# 09_Clock.net
KiCad netlist of a schematic drawn in Altium Designer
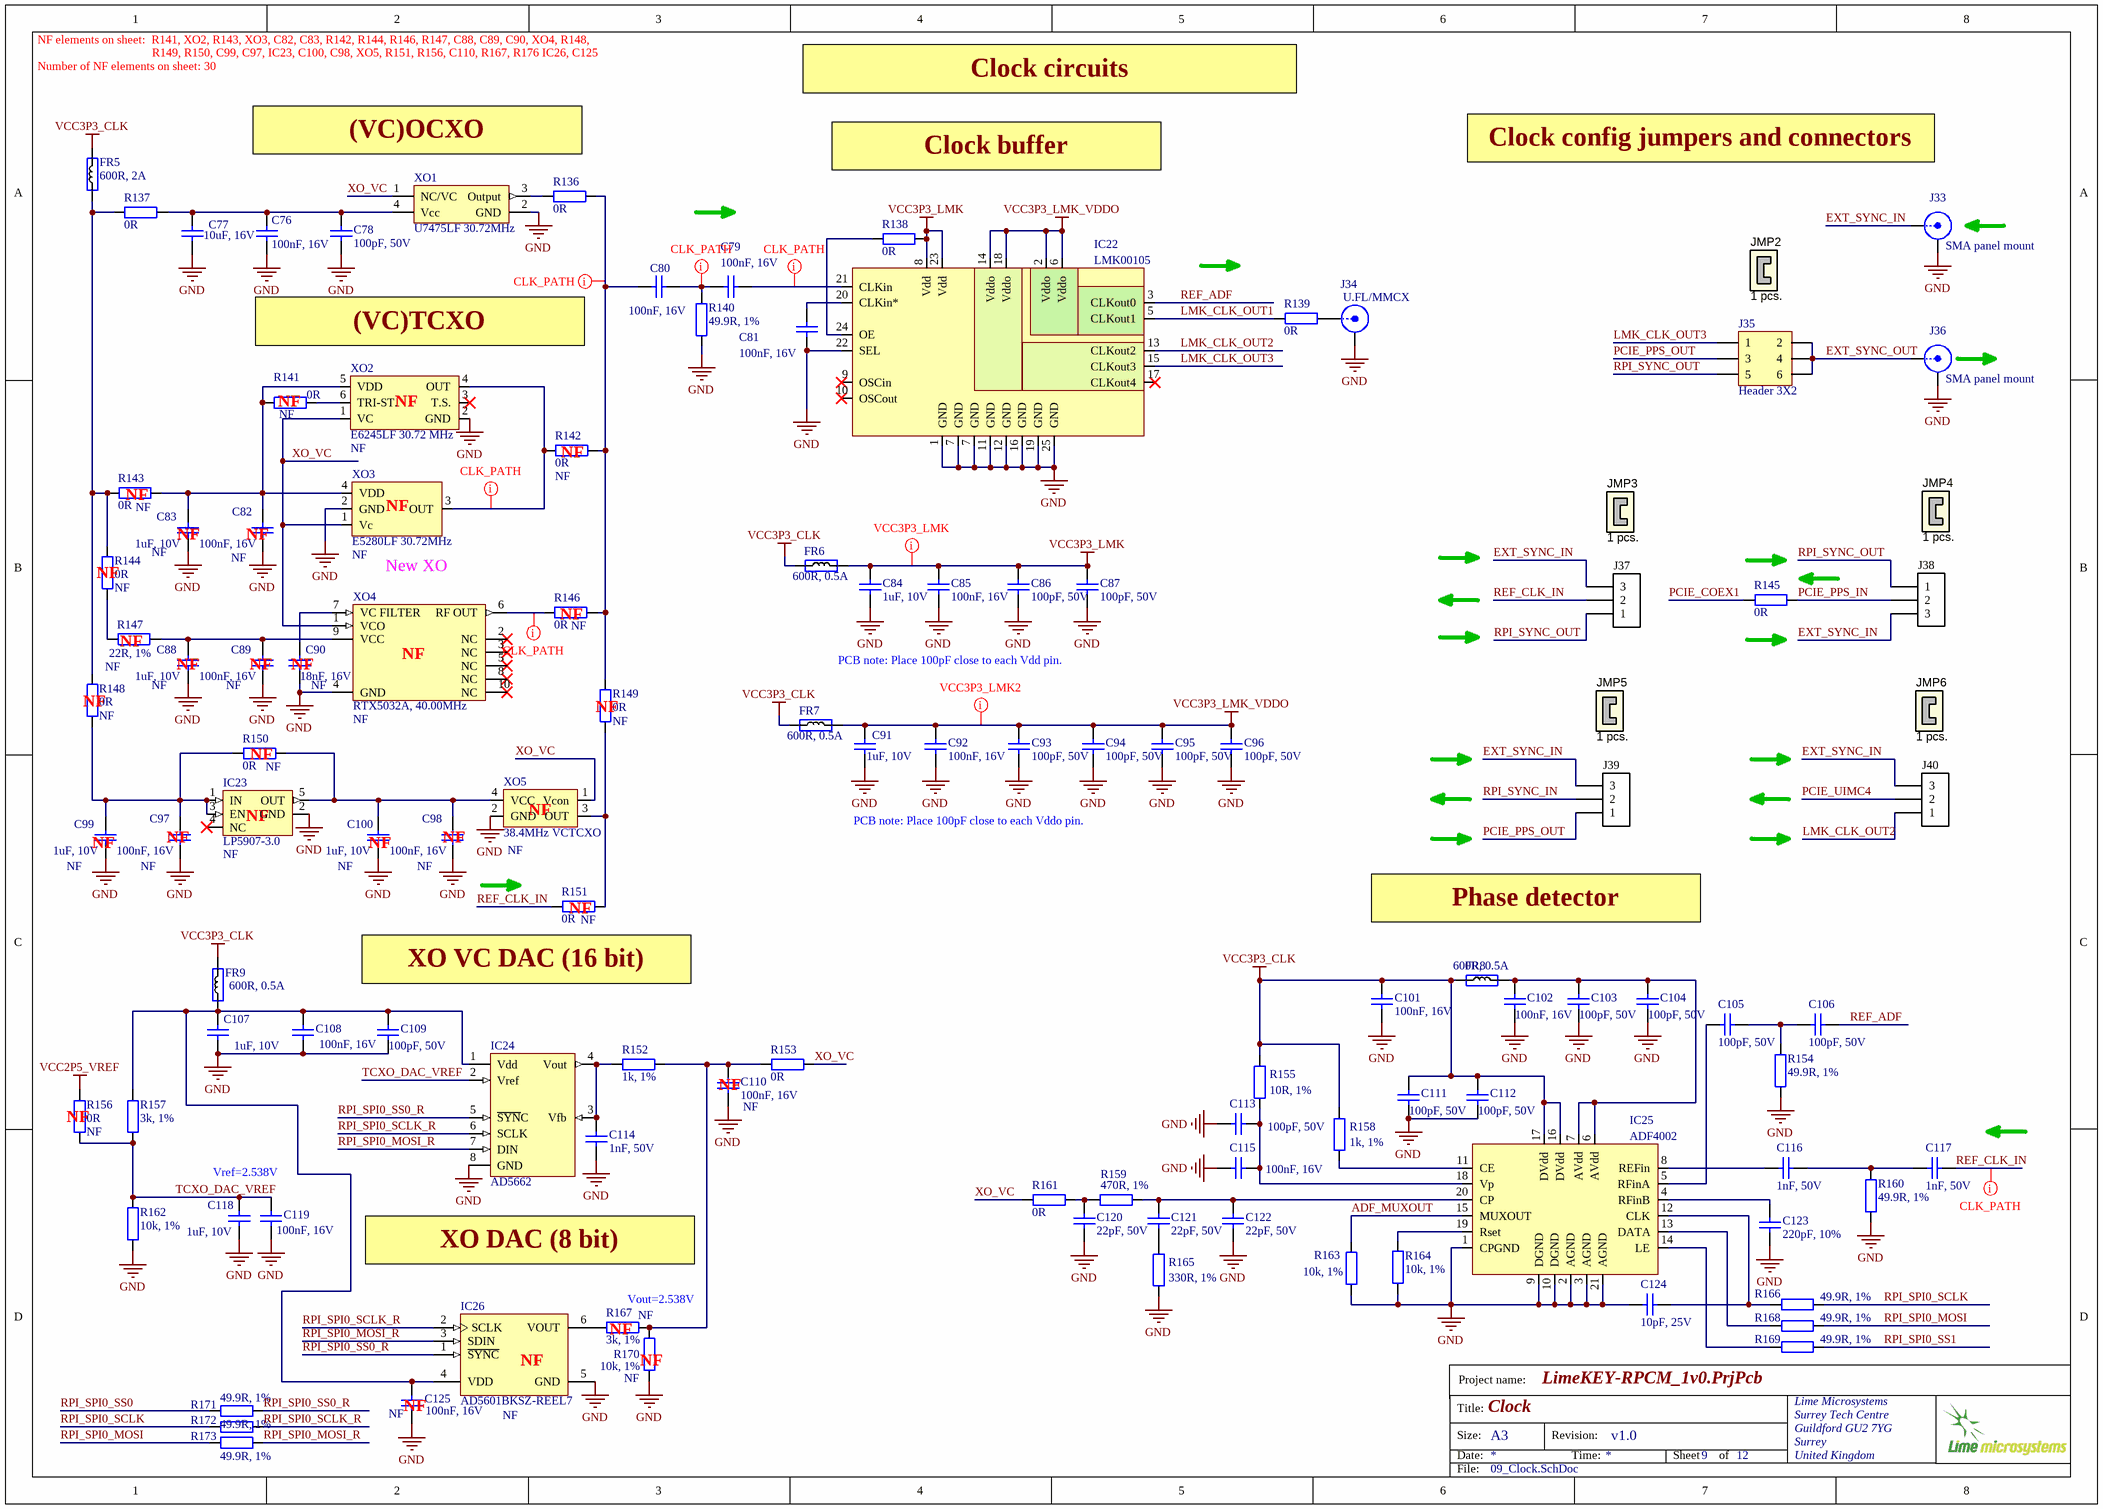
[diagram p0: 09_Clock.SchDoc]

(export (version "E")
  (design (tool "Eeschema 10.0.6"))
  (components
    (comp (ref "C76")
      (value "100nF, 16V")
      (footprint "CAP0402")
      (fields
        (field (name "MANUFACTURER") "Murata Electronics")
        (field (name "TOLERANCE") "10 %")
        (field (name "MANUFACTURER PART NUMBER") "GRM155R71C104KA88D")
      )
      (libsource (lib "LimeMicroAltiumLib_schLib") (part "Cap_0402"))
    )
    (comp (ref "C77")
      (value "10uF, 16V")
      (footprint "CAP0603")
      (fields (field (name "MANUFACTURER") "Yageo") (field (name "TOLERANCE") "±20%"))
      (libsource (lib "LimeMicroAltiumLib_schLib") (part "Cap_0603"))
    )
    (comp (ref "C78")
      (value "100pF, 50V")
      (footprint "CAP0402")
      (fields (field (name "TOLERANCE") "±5%") (field (name "MANUFACTURER") "Yageo"))
      (libsource (lib "LimeMicroAltiumLib_schLib") (part "Cap_0402"))
    )
    (comp (ref "C79")
      (value "100nF, 16V")
      (footprint "CAP0402")
      (fields
        (field (name "MANUFACTURER") "Murata Electronics")
        (field (name "TOLERANCE") "10 %")
        (field (name "MANUFACTURER PART NUMBER") "GRM155R71C104KA88D")
      )
      (libsource (lib "LimeMicroAltiumLib_schLib") (part "Cap_0402"))
    )
    (comp (ref "C80")
      (value "100nF, 16V")
      (footprint "CAP0402")
      (fields
        (field (name "MANUFACTURER") "Murata Electronics")
        (field (name "TOLERANCE") "10 %")
        (field (name "MANUFACTURER PART NUMBER") "GRM155R71C104KA88D")
      )
      (libsource (lib "LimeMicroAltiumLib_schLib") (part "Cap_0402"))
    )
    (comp (ref "C81")
      (value "100nF, 16V")
      (footprint "CAP0402")
      (fields
        (field (name "MANUFACTURER") "Murata Electronics")
        (field (name "TOLERANCE") "10 %")
        (field (name "MANUFACTURER PART NUMBER") "GRM155R71C104KA88D")
      )
      (libsource (lib "LimeMicroAltiumLib_schLib") (part "Cap_0402"))
    )
    (comp (ref "C82")
      (value "100nF, 16V")
      (footprint "CAP0402")
      (fields
        (field (name "ASSEMBLY INFO") "NF")
        (field (name "MANUFACTURER") "Murata Electronics")
        (field (name "TOLERANCE") "10 %")
        (field (name "MANUFACTURER PART NUMBER") "GRM155R71C104KA88D")
      )
      (libsource (lib "LimeMicroAltiumLib_schLib") (part "Cap_0402"))
    )
    (comp (ref "C83")
      (value "1uF, 10V")
      (footprint "CAP0402")
      (description "CAP CER 1UF 10V X5R 0402")
      (fields (field (name "ASSEMBLY INFO") "NF") (field (name "MANUFACTURER") "Yageo"))
      (libsource (lib "LimeMicroAltiumLib_schLib") (part "Cap_0402"))
    )
    (comp (ref "C84")
      (value "1uF, 10V")
      (footprint "CAP0402")
      (description "CAP CER 1UF 10V X5R 0402")
      (fields (field (name "MANUFACTURER") "Yageo") (field (name "TOLERANCE") "±20%"))
      (libsource (lib "LimeMicroAltiumLib_schLib") (part "Cap_0402"))
    )
    (comp (ref "C85")
      (value "100nF, 16V")
      (footprint "CAP0402")
      (fields
        (field (name "MANUFACTURER") "Murata Electronics")
        (field (name "TOLERANCE") "10 %")
        (field (name "MANUFACTURER PART NUMBER") "GRM155R71C104KA88D")
      )
      (libsource (lib "LimeMicroAltiumLib_schLib") (part "Cap_0402"))
    )
    (comp (ref "C86")
      (value "100pF, 50V")
      (footprint "CAP0402")
      (fields (field (name "MANUFACTURER") "Yageo") (field (name "TOLERANCE") "±5%"))
      (libsource (lib "LimeMicroAltiumLib_schLib") (part "Cap_0402"))
    )
    (comp (ref "C87")
      (value "100pF, 50V")
      (footprint "CAP0402")
      (fields (field (name "MANUFACTURER") "Yageo") (field (name "TOLERANCE") "±5%"))
      (libsource (lib "LimeMicroAltiumLib_schLib") (part "Cap_0402"))
    )
    (comp (ref "C88")
      (value "1uF, 10V")
      (footprint "CAP0402")
      (description "CAP CER 1UF 10V X5R 0402")
      (fields (field (name "ASSEMBLY INFO") "NF") (field (name "MANUFACTURER") "Yageo"))
      (libsource (lib "LimeMicroAltiumLib_schLib") (part "Cap_0402"))
    )
    (comp (ref "C89")
      (value "100nF, 16V")
      (footprint "CAP0402")
      (fields
        (field (name "ASSEMBLY INFO") "NF")
        (field (name "MANUFACTURER") "Murata Electronics")
        (field (name "TOLERANCE") "10 %")
        (field (name "MANUFACTURER PART NUMBER") "GRM155R71C104KA88D")
      )
      (libsource (lib "LimeMicroAltiumLib_schLib") (part "Cap_0402"))
    )
    (comp (ref "C90")
      (value "18nF, 16V")
      (footprint "CAP0402")
      (fields
        (field (name "ASSEMBLY INFO") "NF")
        (field (name "MANUFACTURER") "Yageo")
        (field (name "TOLERANCE") "±10%")
      )
      (libsource (lib "LimeMicroAltiumLib_schLib") (part "Cap_0402"))
    )
    (comp (ref "C91")
      (value "1uF, 10V")
      (footprint "CAP0402")
      (description "CAP CER 1UF 10V X5R 0402")
      (fields (field (name "MANUFACTURER") "Yageo") (field (name "TOLERANCE") "±20%"))
      (libsource (lib "LimeMicroAltiumLib_schLib") (part "Cap_0402"))
    )
    (comp (ref "C92")
      (value "100nF, 16V")
      (footprint "CAP0402")
      (fields
        (field (name "MANUFACTURER") "Murata Electronics")
        (field (name "TOLERANCE") "10 %")
        (field (name "MANUFACTURER PART NUMBER") "GRM155R71C104KA88D")
      )
      (libsource (lib "LimeMicroAltiumLib_schLib") (part "Cap_0402"))
    )
    (comp (ref "C93")
      (value "100pF, 50V")
      (footprint "CAP0402")
      (fields (field (name "MANUFACTURER") "Yageo") (field (name "TOLERANCE") "±5%"))
      (libsource (lib "LimeMicroAltiumLib_schLib") (part "Cap_0402"))
    )
    (comp (ref "C94")
      (value "100pF, 50V")
      (footprint "CAP0402")
      (fields (field (name "MANUFACTURER") "Yageo") (field (name "TOLERANCE") "±5%"))
      (libsource (lib "LimeMicroAltiumLib_schLib") (part "Cap_0402"))
    )
    (comp (ref "C95")
      (value "100pF, 50V")
      (footprint "CAP0402")
      (fields (field (name "MANUFACTURER") "Yageo") (field (name "TOLERANCE") "±5%"))
      (libsource (lib "LimeMicroAltiumLib_schLib") (part "Cap_0402"))
    )
    (comp (ref "C96")
      (value "100pF, 50V")
      (footprint "CAP0402")
      (fields (field (name "MANUFACTURER") "Yageo") (field (name "TOLERANCE") "±5%"))
      (libsource (lib "LimeMicroAltiumLib_schLib") (part "Cap_0402"))
    )
    (comp (ref "C97")
      (value "100nF, 16V")
      (footprint "CAP0402")
      (fields
        (field (name "ASSEMBLY INFO") "NF")
        (field (name "MANUFACTURER") "Murata Electronics")
        (field (name "TOLERANCE") "10 %")
        (field (name "MANUFACTURER PART NUMBER") "GRM155R71C104KA88D")
      )
      (libsource (lib "") (part "Cap_0402_1"))
    )
    (comp (ref "C98")
      (value "100nF, 16V")
      (footprint "CAP0402")
      (fields
        (field (name "ASSEMBLY INFO") "NF")
        (field (name "MANUFACTURER") "Murata Electronics")
        (field (name "TOLERANCE") "10 %")
        (field (name "MANUFACTURER PART NUMBER") "GRM155R71C104KA88D")
      )
      (libsource (lib "") (part "Cap_0402_1"))
    )
    (comp (ref "C99")
      (value "1uF, 10V")
      (footprint "CAP0402")
      (fields (field (name "ASSEMBLY INFO") "NF") (field (name "MANUFACTURER") "Yageo"))
      (libsource (lib "") (part "Cap_0402_1"))
    )
    (comp (ref "C100")
      (value "1uF, 10V")
      (footprint "CAP0402")
      (fields (field (name "ASSEMBLY INFO") "NF") (field (name "MANUFACTURER") "Yageo"))
      (libsource (lib "") (part "Cap_0402_1"))
    )
    (comp (ref "C101")
      (value "100nF, 16V")
      (footprint "CAP0402")
      (fields
        (field (name "MANUFACTURER") "Murata Electronics")
        (field (name "TOLERANCE") "10 %")
        (field (name "MANUFACTURER PART NUMBER") "GRM155R71C104KA88D")
      )
      (libsource (lib "LimeMicroAltiumLib_schLib") (part "Cap_0402"))
    )
    (comp (ref "C102")
      (value "100nF, 16V")
      (footprint "CAP0402")
      (fields
        (field (name "MANUFACTURER") "Murata Electronics")
        (field (name "TOLERANCE") "10 %")
        (field (name "MANUFACTURER PART NUMBER") "GRM155R71C104KA88D")
      )
      (libsource (lib "LimeMicroAltiumLib_schLib") (part "Cap_0402"))
    )
    (comp (ref "C103")
      (value "100pF, 50V")
      (footprint "CAP0402")
      (fields (field (name "MANUFACTURER") "Yageo") (field (name "TOLERANCE") "±5%"))
      (libsource (lib "LimeMicroAltiumLib_schLib") (part "Cap_0402"))
    )
    (comp (ref "C104")
      (value "100pF, 50V")
      (footprint "CAP0402")
      (fields (field (name "MANUFACTURER") "Yageo") (field (name "TOLERANCE") "±5%"))
      (libsource (lib "LimeMicroAltiumLib_schLib") (part "Cap_0402"))
    )
    (comp (ref "C105")
      (value "100pF, 50V")
      (footprint "CAP0402")
      (fields (field (name "MANUFACTURER") "Yageo") (field (name "TOLERANCE") "±5%"))
      (libsource (lib "LimeMicroAltiumLib_schLib") (part "Cap_0402"))
    )
    (comp (ref "C106")
      (value "100pF, 50V")
      (footprint "CAP0402")
      (fields (field (name "MANUFACTURER") "Yageo") (field (name "TOLERANCE") "±5%"))
      (libsource (lib "LimeMicroAltiumLib_schLib") (part "Cap_0402"))
    )
    (comp (ref "C107")
      (value "1uF, 10V")
      (footprint "CAP0402")
      (description "CAP CER 1UF 10V X5R 0402")
      (fields (field (name "MANUFACTURER") "Yageo") (field (name "TOLERANCE") "±20%"))
      (libsource (lib "LimeMicroAltiumLib_schLib") (part "Cap_0402"))
    )
    (comp (ref "C108")
      (value "100nF, 16V")
      (footprint "CAP0402")
      (fields
        (field (name "TOLERANCE") "10 %")
        (field (name "MANUFACTURER") "Murata Electronics")
        (field (name "MANUFACTURER PART NUMBER") "GRM155R71C104KA88D")
      )
      (libsource (lib "LimeFPGAboard_schLib") (part "Cap_0603"))
    )
    (comp (ref "C109")
      (value "100pF, 50V")
      (footprint "CAP0402")
      (fields (field (name "MANUFACTURER") "Yageo") (field (name "TOLERANCE") "±5%"))
      (libsource (lib "LimeMicroAltiumLib_schLib") (part "Cap_0402"))
    )
    (comp (ref "C110")
      (value "100nF, 16V")
      (footprint "CAP0402")
      (fields
        (field (name "ASSEMBLY INFO") "NF")
        (field (name "MANUFACTURER") "Murata Electronics")
        (field (name "TOLERANCE") "10 %")
        (field (name "MANUFACTURER PART NUMBER") "GRM155R71C104KA88D")
      )
      (libsource (lib "LimeMicroAltiumLib_schLib") (part "Cap_0402"))
    )
    (comp (ref "C111")
      (value "100pF, 50V")
      (footprint "CAP0402")
      (fields (field (name "MANUFACTURER") "Yageo") (field (name "TOLERANCE") "±5%"))
      (libsource (lib "LimeMicroAltiumLib_schLib") (part "Cap_0402"))
    )
    (comp (ref "C112")
      (value "100pF, 50V")
      (footprint "CAP0402")
      (fields (field (name "MANUFACTURER") "Yageo") (field (name "TOLERANCE") "±5%"))
      (libsource (lib "LimeMicroAltiumLib_schLib") (part "Cap_0402"))
    )
    (comp (ref "C113")
      (value "100pF, 50V")
      (footprint "CAP0402")
      (fields (field (name "MANUFACTURER") "Yageo") (field (name "TOLERANCE") "±5%"))
      (libsource (lib "LimeMicroAltiumLib_schLib") (part "Cap_0402"))
    )
    (comp (ref "C114")
      (value "1nF, 50V")
      (footprint "CAP0402")
      (fields
        (field (name "TOLERANCE") "±10%")
        (field (name "MANUFACTURER") "Murata Electronics North America")
      )
      (libsource (lib "LimeMicroAltiumLib_schLib") (part "Cap_0402"))
    )
    (comp (ref "C115")
      (value "100nF, 16V")
      (footprint "CAP0402")
      (fields
        (field (name "MANUFACTURER") "Murata Electronics")
        (field (name "TOLERANCE") "10 %")
        (field (name "MANUFACTURER PART NUMBER") "GRM155R71C104KA88D")
      )
      (libsource (lib "LimeMicroAltiumLib_schLib") (part "Cap_0402"))
    )
    (comp (ref "C116")
      (value "1nF, 50V")
      (footprint "CAP0402")
      (fields
        (field (name "TOLERANCE") "±10%")
        (field (name "MANUFACTURER") "Murata Electronics North America")
      )
      (libsource (lib "LimeMicroAltiumLib_schLib") (part "Cap_0402"))
    )
    (comp (ref "C117")
      (value "1nF, 50V")
      (footprint "CAP0402")
      (fields
        (field (name "TOLERANCE") "±10%")
        (field (name "MANUFACTURER") "Murata Electronics North America")
      )
      (libsource (lib "LimeMicroAltiumLib_schLib") (part "Cap_0402"))
    )
    (comp (ref "C118")
      (value "1uF, 10V")
      (footprint "CAP0402")
      (description "CAP CER 1UF 10V X5R 0402")
      (fields (field (name "MANUFACTURER") "Yageo") (field (name "TOLERANCE") "±20%"))
      (libsource (lib "LimeMicroAltiumLib_schLib") (part "Cap_0402"))
    )
    (comp (ref "C119")
      (value "100nF, 16V")
      (footprint "CAP0402")
      (fields
        (field (name "TOLERANCE") "10 %")
        (field (name "MANUFACTURER") "Murata Electronics")
        (field (name "MANUFACTURER PART NUMBER") "GRM155R71C104KA88D")
      )
      (libsource (lib "LimeFPGAboard_schLib") (part "Cap_0603"))
    )
    (comp (ref "C120")
      (value "22pF, 50V")
      (footprint "CAP0402")
      (fields (field (name "TOLERANCE") "±5%") (field (name "MANUFACTURER") "Yageo"))
      (libsource (lib "LimeMicroAltiumLib_schLib") (part "Cap_0402"))
    )
    (comp (ref "C121")
      (value "22pF, 50V")
      (footprint "CAP0402")
      (fields (field (name "TOLERANCE") "±5%") (field (name "MANUFACTURER") "Yageo"))
      (libsource (lib "LimeMicroAltiumLib_schLib") (part "Cap_0402"))
    )
    (comp (ref "C122")
      (value "22pF, 50V")
      (footprint "CAP0402")
      (fields (field (name "TOLERANCE") "±5%") (field (name "MANUFACTURER") "Yageo"))
      (libsource (lib "LimeMicroAltiumLib_schLib") (part "Cap_0402"))
    )
    (comp (ref "C123")
      (value "220pF, 10%")
      (footprint "CAP0402")
      (fields (field (name "MANUFACTURER") "Yageo") (field (name "TOLERANCE") "±10%"))
      (libsource (lib "LimeMicroAltiumLib_schLib") (part "Cap_0402"))
    )
    (comp (ref "C124")
      (value "10pF, 25V")
      (footprint "CAP0402")
      (fields (field (name "MANUFACTURER") "AVX"))
      (libsource (lib "LimeMicroAltiumLib_schLib") (part "Cap_0402"))
    )
    (comp (ref "C125")
      (value "100nF, 16V")
      (footprint "CAP0402")
      (fields
        (field (name "TOLERANCE") "10 %")
        (field (name "MANUFACTURER") "Murata Electronics")
        (field (name "MANUFACTURER PART NUMBER") "GRM155R71C104KA88D")
        (field (name "ASSEMBLY INFO") "NF")
      )
      (libsource (lib "LimeFPGAboard_schLib") (part "Cap_0603"))
    )
    (comp (ref "FR5")
      (value "600R, 2A")
      (footprint "RES0805")
      (fields (field (name "MANUFACTURER") "TDK Corporation"))
      (libsource (lib "LimeFPGAboard_schLib") (part "Ferrite"))
    )
    (comp (ref "FR6")
      (value "600R, 0.5A")
      (footprint "RES0402")
      (fields (field (name "MANUFACTURER") "Murata") (field (name "TOLERANCE") "25%"))
      (libsource (lib "LimeMicroAltiumLib_schLib") (part "Ferrite"))
    )
    (comp (ref "FR7")
      (value "600R, 0.5A")
      (footprint "RES0402")
      (fields (field (name "MANUFACTURER") "Murata") (field (name "TOLERANCE") "25%"))
      (libsource (lib "LimeMicroAltiumLib_schLib") (part "Ferrite"))
    )
    (comp (ref "FR8")
      (value "600R, 0.5A")
      (footprint "RES0402")
      (fields (field (name "MANUFACTURER") "Murata") (field (name "TOLERANCE") "25%"))
      (libsource (lib "LimeMicroAltiumLib_schLib") (part "Ferrite"))
    )
    (comp (ref "FR9")
      (value "600R, 0.5A")
      (footprint "RES0402")
      (fields (field (name "MANUFACTURER") "Murata") (field (name "TOLERANCE") "25%"))
      (libsource (lib "LimeMicroAltiumLib_schLib") (part "Ferrite"))
    )
    (comp (ref "IC22")
      (value "LMK00105")
      (footprint "LMK00105SQ")
      (fields (field (name "MANUFACTURER") "Texas Instruments"))
      (libsource (lib "LimeMicroAltiumLib_schLib") (part "LMK00105"))
    )
    (comp (ref "IC23")
      (value "LP5907-3.0")
      (footprint "SOT23-5")
      (fields (field (name "MANUFACTURER") "Texas Instruments") (field (name "ASSEMBLY INFO") "NF"))
      (libsource (lib "LimeMicroAltiumLib_schLib_r01") (part "LP5907"))
    )
    (comp (ref "IC24")
      (value "AD5662")
      (footprint "AD5662_SOT23-8")
      (fields (field (name "MANUFACTURER") "Analog Devices Inc."))
      (libsource (lib "LimeMicroAltiumLib_schLib") (part "AD5662"))
    )
    (comp (ref "IC25")
      (value "ADF4002")
      (footprint "ADF4002")
      (fields (field (name "MANUFACTURER") "Analog Devices Inc"))
      (libsource (lib "LimeMicroAltiumLib_schLib") (part "ADF4002"))
    )
    (comp (ref "IC26")
      (value "AD5601BKSZ-REEL7")
      (footprint "AD5601_SOT23-6")
      (fields
        (field (name "GENERIC PART NUMBER") "AD5601")
        (field (name "MANUFACTURER") "Analog Devices")
        (field (name "ASSEMBLY INFO") "NF")
      )
      (libsource (lib "LimeMicroAltiumLib_schLib") (part "AD5601BKSZ-REEL7"))
    )
    (comp (ref "J33")
      (value "SMA panel mount")
      (footprint "SMA_connector_side")
      (description "CONN SMA JACK STR 50OHM EDGE MNT")
      (fields (field (name "MANUFACTURER") "Linx"))
      (libsource (lib "LimeMicroAltiumLib_schLib") (part "RF_IF_connector"))
    )
    (comp (ref "J34")
      (value "U.FL/MMCX")
      (footprint "MMCX_UFL_conn_u")
      (description "CONN UMC RCPT STR 50 OHM SMD")
      (fields (field (name "MANUFACTURER") "Molex, LLC"))
      (libsource (lib "") (part "RF_IF_connector_1"))
    )
    (comp (ref "J35")
      (value "Header 3X2")
      (footprint "Header3x2")
      (description "Header, 2-Pin, Dual row")
      (fields
        (field (name "MANUFACTURER PART NUMBER") "PH2-06-UA")
        (field (name "MANUFACTURER") "Adam Equipment")
      )
      (libsource (lib "LimeMicroAltiumLib_schLib_r01") (part "Header 3X2"))
    )
    (comp (ref "J36")
      (value "SMA panel mount")
      (footprint "SMA_connector_side")
      (description "CONN SMA JACK STR 50OHM EDGE MNT")
      (fields (field (name "MANUFACTURER") "Linx"))
      (libsource (lib "LimeMicroAltiumLib_schLib") (part "RF_IF_connector"))
    )
    (comp (ref "J37")
      (value "Header 3x1 pin")
      (footprint "HDR_1x3")
      (description "Header, 3-pin")
      (fields
        (field (name "MANUFACTURER PART NUMBER") "61300311121")
        (field (name "MANUFACTURER") "Wurth Electronics")
      )
      (libsource (lib "") (part "Header3P_1"))
    )
    (comp (ref "J38")
      (value "Header 3x1 pin")
      (footprint "HDR_1x3")
      (description "Header, 3-pin")
      (fields
        (field (name "MANUFACTURER PART NUMBER") "61300311121")
        (field (name "MANUFACTURER") "Wurth Electronics")
      )
      (libsource (lib "LimeMicroAltiumLib_schLib_r04") (part "Header3P"))
    )
    (comp (ref "J39")
      (value "Header 3x1 pin")
      (footprint "HDR_1x3")
      (description "Header, 3-pin")
      (fields
        (field (name "MANUFACTURER PART NUMBER") "61300311121")
        (field (name "MANUFACTURER") "Wurth Electronics")
      )
      (libsource (lib "") (part "Header3P_1"))
    )
    (comp (ref "J40")
      (value "Header 3x1 pin")
      (footprint "HDR_1x3")
      (description "Header, 3-pin")
      (fields
        (field (name "MANUFACTURER PART NUMBER") "61300311121")
        (field (name "MANUFACTURER") "Wurth Electronics")
      )
      (libsource (lib "") (part "Header3P_1"))
    )
    (comp (ref "JMP2")
      (value "1 pcs.")
      (description "Shorting Jumper, 2-position, 1.27mm pitch")
      (fields (field (name "MANUFACTURER") "Sullins"))
      (libsource (lib "LimeMicroAltiumLib_schLib") (part "JUMP_2P_CONN_HEADER"))
    )
    (comp (ref "JMP3")
      (value "1 pcs.")
      (description "Shorting Jumper, 2-position, 1.27mm pitch")
      (fields (field (name "MANUFACTURER") "Sullins"))
      (libsource (lib "LimeMicroAltiumLib_schLib") (part "JUMP_2P_CONN_HEADER"))
    )
    (comp (ref "JMP4")
      (value "1 pcs.")
      (description "Shorting Jumper, 2-position, 1.27mm pitch")
      (fields (field (name "MANUFACTURER") "Sullins"))
      (libsource (lib "LimeMicroAltiumLib_schLib") (part "JUMP_2P_CONN_HEADER"))
    )
    (comp (ref "JMP5")
      (value "1 pcs.")
      (description "Shorting Jumper, 2-position, 1.27mm pitch")
      (fields (field (name "MANUFACTURER") "Sullins"))
      (libsource (lib "LimeMicroAltiumLib_schLib") (part "JUMP_2P_CONN_HEADER"))
    )
    (comp (ref "JMP6")
      (value "1 pcs.")
      (description "Shorting Jumper, 2-position, 1.27mm pitch")
      (fields (field (name "MANUFACTURER") "Sullins"))
      (libsource (lib "LimeMicroAltiumLib_schLib") (part "JUMP_2P_CONN_HEADER"))
    )
    (comp (ref "R136")
      (value "0R")
      (footprint "RES0402_v2")
      (fields (field (name "MANUFACTURER") "Yageo") (field (name "TOLERANCE") "Jumper"))
      (libsource (lib "LimeMicroAltiumLib_schLib") (part "Res_0402"))
    )
    (comp (ref "R137")
      (value "0R")
      (footprint "RES0402")
      (fields (field (name "MANUFACTURER") "Yageo") (field (name "TOLERANCE") "Jumper"))
      (libsource (lib "LimeMicroAltiumLib_schLib") (part "Res_0402"))
    )
    (comp (ref "R138")
      (value "0R")
      (footprint "RES0402")
      (fields (field (name "MANUFACTURER") "Yageo") (field (name "TOLERANCE") "Jumper"))
      (libsource (lib "LimeMicroAltiumLib_schLib") (part "Res_0402"))
    )
    (comp (ref "R139")
      (value "0R")
      (footprint "RES0402")
      (fields (field (name "MANUFACTURER") "Yageo") (field (name "TOLERANCE") "Jumper"))
      (libsource (lib "") (part "Res_0402_1"))
    )
    (comp (ref "R140")
      (value "49.9R, 1%")
      (footprint "RES0402")
      (fields
        (field (name "TOLERANCE") "±1%")
        (field (name "MANUFACTURER") "Samsung Electro-Mechanics America, Inc.")
      )
      (libsource (lib "LimeMicroAltiumLib_schLib") (part "Res_0402"))
    )
    (comp (ref "R141")
      (value "0R")
      (footprint "RES0402")
      (fields
        (field (name "ASSEMBLY INFO") "NF")
        (field (name "MANUFACTURER") "Yageo")
        (field (name "TOLERANCE") "Jumper")
      )
      (libsource (lib "LimeMicroAltiumLib_schLib") (part "Res_0402"))
    )
    (comp (ref "R142")
      (value "0R")
      (footprint "RES0402_v2")
      (fields
        (field (name "ASSEMBLY INFO") "NF")
        (field (name "MANUFACTURER") "Yageo")
        (field (name "TOLERANCE") "Jumper")
      )
      (libsource (lib "LimeMicroAltiumLib_schLib") (part "Res_0402"))
    )
    (comp (ref "R143")
      (value "0R")
      (footprint "RES0402")
      (fields
        (field (name "MANUFACTURER") "Yageo")
        (field (name "TOLERANCE") "Jumper")
        (field (name "ASSEMBLY INFO") "NF")
      )
      (libsource (lib "LimeMicroAltiumLib_schLib") (part "Res_0402"))
    )
    (comp (ref "R144")
      (value "0R")
      (footprint "RES0402")
      (fields
        (field (name "ASSEMBLY INFO") "NF")
        (field (name "MANUFACTURER") "Yageo")
        (field (name "TOLERANCE") "Jumper")
      )
      (libsource (lib "LimeMicroAltiumLib_schLib") (part "Res_0402"))
    )
    (comp (ref "R145")
      (value "0R")
      (footprint "RES0402")
      (fields (field (name "MANUFACTURER") "Yageo") (field (name "TOLERANCE") "Jumper"))
      (libsource (lib "") (part "Res_0402_1"))
    )
    (comp (ref "R146")
      (value "0R")
      (footprint "RES0402_v2")
      (fields
        (field (name "ASSEMBLY INFO") "NF")
        (field (name "MANUFACTURER") "Yageo")
        (field (name "TOLERANCE") "Jumper")
      )
      (libsource (lib "LimeMicroAltiumLib_schLib") (part "Res_0402"))
    )
    (comp (ref "R147")
      (value "22R, 1%")
      (footprint "RES0402")
      (fields
        (field (name "TOLERANCE") "±1%")
        (field (name "MANUFACTURER") "Yageo")
        (field (name "ASSEMBLY INFO") "NF")
      )
      (libsource (lib "LimeFPGAboard_schLib") (part "Res_0402"))
    )
    (comp (ref "R148")
      (value "0R")
      (footprint "RES0402")
      (fields
        (field (name "MANUFACTURER") "Yageo")
        (field (name "TOLERANCE") "Jumper")
        (field (name "ASSEMBLY INFO") "NF")
      )
      (libsource (lib "") (part "Res_0402_1"))
    )
    (comp (ref "R149")
      (value "0R")
      (footprint "RES0402_v2")
      (fields
        (field (name "ASSEMBLY INFO") "NF")
        (field (name "MANUFACTURER") "Yageo")
        (field (name "TOLERANCE") "Jumper")
      )
      (libsource (lib "") (part "Res_0402_1"))
    )
    (comp (ref "R150")
      (value "0R")
      (footprint "RES0402")
      (fields
        (field (name "MANUFACTURER") "Yageo")
        (field (name "TOLERANCE") "Jumper")
        (field (name "ASSEMBLY INFO") "NF")
      )
      (libsource (lib "") (part "Res_0402_1"))
    )
    (comp (ref "R151")
      (value "0R")
      (footprint "RES0402_v2")
      (fields
        (field (name "ASSEMBLY INFO") "NF")
        (field (name "MANUFACTURER") "Yageo")
        (field (name "TOLERANCE") "Jumper")
      )
      (libsource (lib "LimeMicroAltiumLib_schLib") (part "Res_0402"))
    )
    (comp (ref "R152")
      (value "1k, 1%")
      (footprint "RES0402")
      (fields (field (name "MANUFACTURER") "Stackpole Electronics Inc") (field (name "TOLERANCE") "±1%"))
      (libsource (lib "LimeMicroAltiumLib_schLib") (part "Res_0402"))
    )
    (comp (ref "R153")
      (value "0R")
      (footprint "RES0402")
      (fields (field (name "MANUFACTURER") "Yageo") (field (name "TOLERANCE") "Jumper"))
      (libsource (lib "LimeMicroAltiumLib_schLib") (part "Res_0402"))
    )
    (comp (ref "R154")
      (value "49.9R, 1%")
      (footprint "RES0402")
      (fields
        (field (name "TOLERANCE") "±1%")
        (field (name "MANUFACTURER") "Samsung Electro-Mechanics America, Inc.")
      )
      (libsource (lib "LimeMicroAltiumLib_schLib") (part "Res_0402"))
    )
    (comp (ref "R155")
      (value "10R, 1%")
      (footprint "RES0402")
      (fields (field (name "MANUFACTURER") "Stackpole Electronics") (field (name "TOLERANCE") "1%"))
      (libsource (lib "LimeMicroAltiumLib_schLib") (part "Res_0402"))
    )
    (comp (ref "R156")
      (value "0R")
      (footprint "RES0402_v2")
      (fields
        (field (name "ASSEMBLY INFO") "NF")
        (field (name "MANUFACTURER") "Yageo")
        (field (name "TOLERANCE") "Jumper")
      )
      (libsource (lib "LimeMicroAltiumLib_schLib") (part "Res_0402"))
    )
    (comp (ref "R157")
      (value "3k, 1%")
      (footprint "RES0402")
      (fields (field (name "TOLERANCE") "±1%") (field (name "MANUFACTURER") "Vishay Dale"))
      (libsource (lib "LimeMicroAltiumLib_schLib") (part "Res_0402"))
    )
    (comp (ref "R158")
      (value "1k, 1%")
      (footprint "RES0402")
      (fields (field (name "MANUFACTURER") "Stackpole Electronics Inc") (field (name "TOLERANCE") "±1%"))
      (libsource (lib "LimeMicroAltiumLib_schLib") (part "Res_0402"))
    )
    (comp (ref "R159")
      (value "470R, 1%")
      (footprint "RES0402")
      (fields (field (name "TOLERANCE") "1%") (field (name "MANUFACTURER") "Yageo"))
      (libsource (lib "") (part "Res_0402_1"))
    )
    (comp (ref "R160")
      (value "49.9R, 1%")
      (footprint "RES0402")
      (fields
        (field (name "TOLERANCE") "±1%")
        (field (name "MANUFACTURER") "Samsung Electro-Mechanics America, Inc.")
      )
      (libsource (lib "LimeMicroAltiumLib_schLib") (part "Res_0402"))
    )
    (comp (ref "R161")
      (value "0R")
      (footprint "RES0402")
      (fields (field (name "MANUFACTURER") "Yageo") (field (name "TOLERANCE") "Jumper"))
      (libsource (lib "LimeMicroAltiumLib_schLib") (part "Res_0402"))
    )
    (comp (ref "R162")
      (value "10k, 1%")
      (footprint "RES0402")
      (fields (field (name "MANUFACTURER") "Yageo") (field (name "TOLERANCE") "±1%"))
      (libsource (lib "LimeMicroAltiumLib_schLib") (part "Res_0402"))
    )
    (comp (ref "R163")
      (value "10k, 1%")
      (footprint "RES0402")
      (fields (field (name "MANUFACTURER") "Yageo") (field (name "TOLERANCE") "±1%"))
      (libsource (lib "LimeMicroAltiumLib_schLib") (part "Res_0402"))
    )
    (comp (ref "R164")
      (value "10k, 1%")
      (footprint "RES0402")
      (fields (field (name "MANUFACTURER") "Yageo") (field (name "TOLERANCE") "±1%"))
      (libsource (lib "LimeMicroAltiumLib_schLib") (part "Res_0402"))
    )
    (comp (ref "R165")
      (value "330R, 1%")
      (footprint "RES0402")
      (fields (field (name "MANUFACTURER") "Yageo") (field (name "TOLERANCE") "1%"))
      (libsource (lib "LimeMicroAltiumLib_schLib") (part "Res_0402"))
    )
    (comp (ref "R166")
      (value "49.9R, 1%")
      (footprint "RES0402")
      (fields
        (field (name "TOLERANCE") "±1%")
        (field (name "MANUFACTURER") "Samsung Electro-Mechanics America, Inc.")
      )
      (libsource (lib "LimeMicroAltiumLib_schLib") (part "Res_0402"))
    )
    (comp (ref "R167")
      (value "3k, 1%")
      (footprint "RES0402")
      (fields
        (field (name "ASSEMBLY INFO") "NF")
        (field (name "TOLERANCE") "±1%")
        (field (name "MANUFACTURER") "Vishay Dale")
      )
      (libsource (lib "LimeMicroAltiumLib_schLib") (part "Res_0402"))
    )
    (comp (ref "R168")
      (value "49.9R, 1%")
      (footprint "RES0402")
      (fields
        (field (name "TOLERANCE") "±1%")
        (field (name "MANUFACTURER") "Samsung Electro-Mechanics America, Inc.")
      )
      (libsource (lib "LimeMicroAltiumLib_schLib") (part "Res_0402"))
    )
    (comp (ref "R169")
      (value "49.9R, 1%")
      (footprint "RES0402")
      (fields
        (field (name "TOLERANCE") "±1%")
        (field (name "MANUFACTURER") "Samsung Electro-Mechanics America, Inc.")
      )
      (libsource (lib "LimeMicroAltiumLib_schLib") (part "Res_0402"))
    )
    (comp (ref "R170")
      (value "10k, 1%")
      (footprint "RES0402")
      (fields
        (field (name "ASSEMBLY INFO") "NF")
        (field (name "MANUFACTURER") "Yageo")
        (field (name "TOLERANCE") "±1%")
      )
      (libsource (lib "LimeMicroAltiumLib_schLib") (part "Res_0402"))
    )
    (comp (ref "R171")
      (value "49.9R, 1%")
      (footprint "RES0402")
      (fields
        (field (name "TOLERANCE") "±1%")
        (field (name "MANUFACTURER") "Samsung Electro-Mechanics America, Inc.")
      )
      (libsource (lib "LimeMicroAltiumLib_schLib") (part "Res_0402"))
    )
    (comp (ref "R172")
      (value "49.9R, 1%")
      (footprint "RES0402")
      (fields
        (field (name "TOLERANCE") "±1%")
        (field (name "MANUFACTURER") "Samsung Electro-Mechanics America, Inc.")
      )
      (libsource (lib "LimeMicroAltiumLib_schLib") (part "Res_0402"))
    )
    (comp (ref "R173")
      (value "49.9R, 1%")
      (footprint "RES0402")
      (fields
        (field (name "TOLERANCE") "±1%")
        (field (name "MANUFACTURER") "Samsung Electro-Mechanics America, Inc.")
      )
      (libsource (lib "LimeMicroAltiumLib_schLib") (part "Res_0402"))
    )
    (comp (ref "XO1")
      (value "U7475LF 30.72MHz")
      (footprint "AOCJYR-10.000MHz")
      (fields (field (name "MANUFACTURER") "Rakon"))
      (libsource (lib "LimeMicroAltiumLib_schLib") (part "AOCJYR-10.000MHz"))
    )
    (comp (ref "XO2")
      (value "E6245LF 30.72 MHz")
      (footprint "RAKON_RPT7050A")
      (fields (field (name "ASSEMBLY INFO") "NF") (field (name "MANUFACTURER") "Rakon"))
      (libsource (lib "LimeMicroAltiumLib_schLib") (part "RPT7050A"))
    )
    (comp (ref "XO3")
      (value "E5280LF 30.72MHz")
      (footprint "RAKON_TXCO")
      (fields (field (name "ASSEMBLY INFO") "NF") (field (name "MANUFACTURER") "Rakon"))
      (libsource (lib "LimeMicroAltiumLib_schLib") (part "TXCO"))
    )
    (comp (ref "XO4")
      (value "RTX5032A, 40.00MHz")
      (footprint "RAKON_RTX5032A")
      (fields (field (name "ASSEMBLY INFO") "NF") (field (name "MANUFACTURER") "Rakon"))
      (libsource (lib "LimeMicroAltiumLib_schLib") (part "Rakon_RTX5032A"))
    )
    (comp (ref "XO5")
      (value "38.4MHz VCTCXO")
      (footprint "CRYSTAL_4-LCC_2P5x2P0")
      (description "Oscillator Crystal")
      (fields (field (name "MANUFACTURER") "Abracon") (field (name "ASSEMBLY INFO") "NF"))
      (libsource (lib "LimeMicroAltiumLib_schLib_r01") (part "ASVTX-12-A-38.400MHZ-H10-T_CRYSTAL"))
    )
  )
  (nets
    (net (code "1") (name "/ADF_MUXOUT") (class "Default")
      (node (ref "IC25") (pin "15") (pinfunction "MUXOUT_15") (pintype "passive"))
      (node (ref "R163") (pin "1") (pinfunction "1_1") (pintype "passive"))
    )
    (net (code "2") (name "/EXT_SYNC_IN") (class "Default")
      (node (ref "J33") (pin "1") (pinfunction "X_1") (pintype "passive"))
      (node (ref "J37") (pin "3") (pinfunction "3_3") (pintype "passive"))
      (node (ref "J38") (pin "3") (pinfunction "3_3") (pintype "passive"))
      (node (ref "J39") (pin "3") (pinfunction "3_3") (pintype "passive"))
      (node (ref "J40") (pin "3") (pinfunction "3_3") (pintype "passive"))
    )
    (net (code "3") (name "/EXT_SYNC_OUT") (class "Default")
      (node (ref "J35") (pin "2") (pinfunction "2_2") (pintype "passive"))
      (node (ref "J35") (pin "4") (pinfunction "4_4") (pintype "passive"))
      (node (ref "J35") (pin "6") (pinfunction "6_6") (pintype "passive"))
      (node (ref "J36") (pin "1") (pinfunction "X_1") (pintype "passive"))
    )
    (net (code "4") (name "/LMK_CLK_OUT1") (class "Default")
      (node (ref "IC22") (pin "5") (pinfunction "CLKout1_5") (pintype "passive"))
      (node (ref "R139") (pin "2") (pinfunction "2_2") (pintype "passive"))
    )
    (net (code "5") (name "/LMK_CLK_OUT2") (class "Default")
      (node (ref "IC22") (pin "13") (pinfunction "CLKout2_13") (pintype "passive"))
      (node (ref "J40") (pin "1") (pinfunction "1_1") (pintype "passive"))
    )
    (net (code "6") (name "/LMK_CLK_OUT3") (class "Default")
      (node (ref "IC22") (pin "15") (pinfunction "CLKout3_15") (pintype "passive"))
      (node (ref "J35") (pin "1") (pinfunction "1_1") (pintype "passive"))
    )
    (net (code "7") (name "/PCIE_COEX1") (class "Default")
      (node (ref "R145") (pin "2") (pinfunction "2_2") (pintype "passive"))
    )
    (net (code "9") (name "/PCIE_PPS_OUT") (class "Default")
      (node (ref "J35") (pin "3") (pinfunction "3_3") (pintype "passive"))
      (node (ref "J39") (pin "1") (pinfunction "1_1") (pintype "passive"))
    )
    (net (code "10") (name "/PCIE_UIMC4") (class "Default")
      (node (ref "J40") (pin "2") (pinfunction "2_2") (pintype "passive"))
    )
    (net (code "11") (name "/REF_ADF") (class "Default")
      (node (ref "C106") (pin "2") (pinfunction "2_2") (pintype "passive"))
      (node (ref "IC22") (pin "3") (pinfunction "CLKout0_3") (pintype "passive"))
    )
    (net (code "12") (name "/REF_CLK_IN") (class "Default")
      (node (ref "C117") (pin "2") (pinfunction "2_2") (pintype "passive"))
      (node (ref "J37") (pin "2") (pinfunction "2_2") (pintype "passive"))
      (node (ref "R151") (pin "2") (pinfunction "2_2") (pintype "passive"))
    )
    (net (code "13") (name "/RPI_SPI0_MOSI") (class "Default")
      (node (ref "R168") (pin "1") (pinfunction "1_1") (pintype "passive"))
      (node (ref "R173") (pin "2") (pinfunction "2_2") (pintype "passive"))
    )
    (net (code "14") (name "/RPI_SPI0_MOSI_R") (class "Default")
      (node (ref "IC24") (pin "7") (pinfunction "DIN_7") (pintype "input"))
      (node (ref "IC26") (pin "3") (pinfunction "SDIN_3") (pintype "input"))
      (node (ref "R173") (pin "1") (pinfunction "1_1") (pintype "passive"))
    )
    (net (code "15") (name "/RPI_SPI0_SCLK") (class "Default")
      (node (ref "R166") (pin "1") (pinfunction "1_1") (pintype "passive"))
      (node (ref "R172") (pin "2") (pinfunction "2_2") (pintype "passive"))
    )
    (net (code "16") (name "/RPI_SPI0_SCLK_R") (class "Default")
      (node (ref "IC24") (pin "6") (pinfunction "SCLK_6") (pintype "input"))
      (node (ref "IC26") (pin "2") (pinfunction "SCLK_2") (pintype "input"))
      (node (ref "R172") (pin "1") (pinfunction "1_1") (pintype "passive"))
    )
    (net (code "17") (name "/RPI_SPI0_SS0") (class "Default")
      (node (ref "R171") (pin "2") (pinfunction "2_2") (pintype "passive"))
    )
    (net (code "18") (name "/RPI_SPI0_SS0_R") (class "Default")
      (node (ref "IC24") (pin "5") (pinfunction "~{SYN}C_5") (pintype "input"))
      (node (ref "IC26") (pin "1") (pinfunction "~{SYNC}_1") (pintype "input"))
      (node (ref "R171") (pin "1") (pinfunction "1_1") (pintype "passive"))
    )
    (net (code "19") (name "/RPI_SPI0_SS1") (class "Default")
      (node (ref "R169") (pin "1") (pinfunction "1_1") (pintype "passive"))
    )
    (net (code "20") (name "/RPI_SYNC_IN") (class "Default")
      (node (ref "J39") (pin "2") (pinfunction "2_2") (pintype "passive"))
    )
    (net (code "21") (name "/RPI_SYNC_OUT") (class "Default")
      (node (ref "J35") (pin "5") (pinfunction "5_5") (pintype "passive"))
      (node (ref "J37") (pin "1") (pinfunction "1_1") (pintype "passive"))
      (node (ref "J38") (pin "1") (pinfunction "1_1") (pintype "passive"))
    )
    (net (code "22") (name "/TCXO_DAC_VREF") (class "Default")
      (node (ref "C118") (pin "2") (pinfunction "2_2") (pintype "passive"))
      (node (ref "C119") (pin "1") (pinfunction "1_1") (pintype "passive"))
      (node (ref "IC24") (pin "2") (pinfunction "Vref_2") (pintype "input"))
      (node (ref "R156") (pin "1") (pinfunction "1_1") (pintype "passive"))
      (node (ref "R157") (pin "1") (pinfunction "1_1") (pintype "passive"))
      (node (ref "R162") (pin "1") (pinfunction "1_1") (pintype "passive"))
    )
    (net (code "23") (name "/XO_VC") (class "Default")
      (node (ref "R153") (pin "1") (pinfunction "1_1") (pintype "passive"))
      (node (ref "R161") (pin "2") (pinfunction "2_2") (pintype "passive"))
      (node (ref "XO1") (pin "1") (pinfunction "NC/VC_1") (pintype "passive"))
      (node (ref "XO2") (pin "1") (pinfunction "VC_1") (pintype "passive"))
      (node (ref "XO3") (pin "1") (pinfunction "Vc_1") (pintype "passive"))
      (node (ref "XO4") (pin "1") (pinfunction "VCO_1") (pintype "input"))
      (node (ref "XO5") (pin "1") (pinfunction "Vcon_1") (pintype "passive"))
    )
    (net (code "24") (name "GND") (class "Default")
      (node (ref "C100") (pin "1") (pinfunction "1_1") (pintype "passive"))
      (node (ref "C101") (pin "1") (pinfunction "1_1") (pintype "passive"))
      (node (ref "C102") (pin "1") (pinfunction "1_1") (pintype "passive"))
      (node (ref "C103") (pin "2") (pinfunction "2_2") (pintype "passive"))
      (node (ref "C104") (pin "2") (pinfunction "2_2") (pintype "passive"))
      (node (ref "C107") (pin "1") (pinfunction "1_1") (pintype "passive"))
      (node (ref "C108") (pin "2") (pinfunction "2_2") (pintype "passive"))
      (node (ref "C109") (pin "2") (pinfunction "2_2") (pintype "passive"))
      (node (ref "C110") (pin "1") (pinfunction "1_1") (pintype "passive"))
      (node (ref "C111") (pin "2") (pinfunction "2_2") (pintype "passive"))
      (node (ref "C112") (pin "2") (pinfunction "2_2") (pintype "passive"))
      (node (ref "C113") (pin "1") (pinfunction "1_1") (pintype "passive"))
      (node (ref "C114") (pin "2") (pinfunction "2_2") (pintype "passive"))
      (node (ref "C115") (pin "2") (pinfunction "2_2") (pintype "passive"))
      (node (ref "C118") (pin "1") (pinfunction "1_1") (pintype "passive"))
      (node (ref "C119") (pin "2") (pinfunction "2_2") (pintype "passive"))
      (node (ref "C120") (pin "1") (pinfunction "1_1") (pintype "passive"))
      (node (ref "C122") (pin "1") (pinfunction "1_1") (pintype "passive"))
      (node (ref "C123") (pin "2") (pinfunction "2_2") (pintype "passive"))
      (node (ref "C124") (pin "1") (pinfunction "1_1") (pintype "passive"))
      (node (ref "C125") (pin "2") (pinfunction "2_2") (pintype "passive"))
      (node (ref "C76") (pin "1") (pinfunction "1_1") (pintype "passive"))
      (node (ref "C77") (pin "1") (pinfunction "1_1") (pintype "passive"))
      (node (ref "C78") (pin "2") (pinfunction "2_2") (pintype "passive"))
      (node (ref "C81") (pin "1") (pinfunction "1_1") (pintype "passive"))
      (node (ref "C82") (pin "1") (pinfunction "1_1") (pintype "passive"))
      (node (ref "C83") (pin "1") (pinfunction "1_1") (pintype "passive"))
      (node (ref "C84") (pin "1") (pinfunction "1_1") (pintype "passive"))
      (node (ref "C85") (pin "1") (pinfunction "1_1") (pintype "passive"))
      (node (ref "C86") (pin "1") (pinfunction "1_1") (pintype "passive"))
      (node (ref "C87") (pin "1") (pinfunction "1_1") (pintype "passive"))
      (node (ref "C88") (pin "1") (pinfunction "1_1") (pintype "passive"))
      (node (ref "C89") (pin "1") (pinfunction "1_1") (pintype "passive"))
      (node (ref "C90") (pin "1") (pinfunction "1_1") (pintype "passive"))
      (node (ref "C91") (pin "1") (pinfunction "1_1") (pintype "passive"))
      (node (ref "C92") (pin "1") (pinfunction "1_1") (pintype "passive"))
      (node (ref "C93") (pin "1") (pinfunction "1_1") (pintype "passive"))
      (node (ref "C94") (pin "1") (pinfunction "1_1") (pintype "passive"))
      (node (ref "C95") (pin "1") (pinfunction "1_1") (pintype "passive"))
      (node (ref "C96") (pin "1") (pinfunction "1_1") (pintype "passive"))
      (node (ref "C97") (pin "1") (pinfunction "1_1") (pintype "passive"))
      (node (ref "C98") (pin "1") (pinfunction "1_1") (pintype "passive"))
      (node (ref "C99") (pin "1") (pinfunction "1_1") (pintype "passive"))
      (node (ref "IC22") (pin "1") (pinfunction "GND_1") (pintype "passive"))
      (node (ref "IC22") (pin "11") (pinfunction "GND_11") (pintype "passive"))
      (node (ref "IC22") (pin "12") (pinfunction "GND_12") (pintype "passive"))
      (node (ref "IC22") (pin "16") (pinfunction "GND_16") (pintype "passive"))
      (node (ref "IC22") (pin "19") (pinfunction "GND_19") (pintype "passive"))
      (node (ref "IC22") (pin "22") (pinfunction "SEL_22") (pintype "passive"))
      (node (ref "IC22") (pin "25") (pinfunction "GND_25") (pintype "passive"))
      (node (ref "IC22") (pin "7") (pinfunction "GND_7") (pintype "passive"))
      (node (ref "IC23") (pin "2") (pinfunction "GND_2") (pintype "passive"))
      (node (ref "IC24") (pin "8") (pinfunction "GND_8") (pintype "passive"))
      (node (ref "IC25") (pin "1") (pinfunction "CPGND_1") (pintype "passive"))
      (node (ref "IC25") (pin "10") (pinfunction "DGND_10") (pintype "passive"))
      (node (ref "IC25") (pin "2") (pinfunction "AGND_2") (pintype "passive"))
      (node (ref "IC25") (pin "21") (pinfunction "AGND_21") (pintype "passive"))
      (node (ref "IC25") (pin "3") (pinfunction "AGND_3") (pintype "passive"))
      (node (ref "IC25") (pin "9") (pinfunction "DGND_9") (pintype "passive"))
      (node (ref "IC26") (pin "5") (pinfunction "GND_5") (pintype "power_in"))
      (node (ref "J33") (pin "2") (pinfunction "Y_2") (pintype "passive"))
      (node (ref "J34") (pin "2") (pinfunction "Y_2") (pintype "passive"))
      (node (ref "J36") (pin "2") (pinfunction "Y_2") (pintype "passive"))
      (node (ref "R140") (pin "1") (pinfunction "1_1") (pintype "passive"))
      (node (ref "R154") (pin "1") (pinfunction "1_1") (pintype "passive"))
      (node (ref "R160") (pin "1") (pinfunction "1_1") (pintype "passive"))
      (node (ref "R162") (pin "2") (pinfunction "2_2") (pintype "passive"))
      (node (ref "R163") (pin "2") (pinfunction "2_2") (pintype "passive"))
      (node (ref "R164") (pin "2") (pinfunction "2_2") (pintype "passive"))
      (node (ref "R165") (pin "1") (pinfunction "1_1") (pintype "passive"))
      (node (ref "R170") (pin "2") (pinfunction "2_2") (pintype "passive"))
      (node (ref "XO1") (pin "2") (pinfunction "GND_2") (pintype "passive"))
      (node (ref "XO2") (pin "2") (pinfunction "GND_2") (pintype "passive"))
      (node (ref "XO3") (pin "2") (pinfunction "GND_2") (pintype "passive"))
      (node (ref "XO4") (pin "4") (pinfunction "GND_4") (pintype "passive"))
      (node (ref "XO5") (pin "2") (pinfunction "GND_2") (pintype "passive"))
    )
    (net (code "25") (name "Net-(C79-Pad2)") (class "Default")
      (node (ref "C79") (pin "2") (pinfunction "2_2") (pintype "passive"))
      (node (ref "C80") (pin "1") (pinfunction "1_1") (pintype "passive"))
      (node (ref "R140") (pin "2") (pinfunction "2_2") (pintype "passive"))
    )
    (net (code "26") (name "Net-(C80-Pad2)") (class "Default")
      (node (ref "C80") (pin "2") (pinfunction "2_2") (pintype "passive"))
      (node (ref "R136") (pin "1") (pinfunction "1_1") (pintype "passive"))
      (node (ref "R142") (pin "1") (pinfunction "1_1") (pintype "passive"))
      (node (ref "R146") (pin "2") (pinfunction "2_2") (pintype "passive"))
      (node (ref "R149") (pin "1") (pinfunction "1_1") (pintype "passive"))
    )
    (net (code "27") (name "Net-(C102-Pad2)") (class "Default")
      (node (ref "C102") (pin "2") (pinfunction "2_2") (pintype "passive"))
      (node (ref "C103") (pin "1") (pinfunction "1_1") (pintype "passive"))
      (node (ref "C104") (pin "1") (pinfunction "1_1") (pintype "passive"))
      (node (ref "FR8") (pin "2") (pinfunction "2_2") (pintype "passive"))
      (node (ref "IC25") (pin "6") (pinfunction "AVdd_6") (pintype "passive"))
      (node (ref "IC25") (pin "7") (pinfunction "AVdd_7") (pintype "passive"))
    )
    (net (code "28") (name "Net-(C105-Pad2)") (class "Default")
      (node (ref "C105") (pin "2") (pinfunction "2_2") (pintype "passive"))
      (node (ref "C106") (pin "1") (pinfunction "1_1") (pintype "passive"))
      (node (ref "R154") (pin "2") (pinfunction "2_2") (pintype "passive"))
    )
    (net (code "29") (name "Net-(C110-Pad2)") (class "Default")
      (node (ref "C110") (pin "2") (pinfunction "2_2") (pintype "passive"))
      (node (ref "R152") (pin "1") (pinfunction "1_1") (pintype "passive"))
      (node (ref "R153") (pin "2") (pinfunction "2_2") (pintype "passive"))
      (node (ref "R167") (pin "1") (pinfunction "1_1") (pintype "passive"))
      (node (ref "R170") (pin "1") (pinfunction "1_1") (pintype "passive"))
    )
    (net (code "30") (name "Net-(C116-Pad2)") (class "Default")
      (node (ref "C116") (pin "2") (pinfunction "2_2") (pintype "passive"))
      (node (ref "C117") (pin "1") (pinfunction "1_1") (pintype "passive"))
      (node (ref "R160") (pin "2") (pinfunction "2_2") (pintype "passive"))
    )
    (net (code "31") (name "Net-(C120-Pad2)") (class "Default")
      (node (ref "C120") (pin "2") (pinfunction "2_2") (pintype "passive"))
      (node (ref "R159") (pin "2") (pinfunction "2_2") (pintype "passive"))
      (node (ref "R161") (pin "1") (pinfunction "1_1") (pintype "passive"))
    )
    (net (code "32") (name "Net-(C121-Pad1)") (class "Default")
      (node (ref "C121") (pin "1") (pinfunction "1_1") (pintype "passive"))
      (node (ref "R165") (pin "2") (pinfunction "2_2") (pintype "passive"))
    )
    (net (code "33") (name "Net-(FR5-Pad2)") (class "Default")
      (node (ref "FR5") (pin "2") (pinfunction "2_2") (pintype "passive"))
      (node (ref "R137") (pin "1") (pinfunction "1_1") (pintype "passive"))
      (node (ref "R143") (pin "2") (pinfunction "2_2") (pintype "passive"))
      (node (ref "R144") (pin "1") (pinfunction "1_1") (pintype "passive"))
      (node (ref "R148") (pin "1") (pinfunction "1_1") (pintype "passive"))
    )
    (net (code "34") (name "Net-(IC22-CLKin)") (class "Default")
      (node (ref "C79") (pin "1") (pinfunction "1_1") (pintype "passive"))
      (node (ref "IC22") (pin "21") (pinfunction "CLKin_21") (pintype "passive"))
    )
    (net (code "35") (name "Net-(IC22-CLKin*)") (class "Default")
      (node (ref "C81") (pin "2") (pinfunction "2_2") (pintype "passive"))
      (node (ref "IC22") (pin "20") (pinfunction "CLKin*_20") (pintype "passive"))
    )
    (net (code "36") (name "Net-(IC22-OE)") (class "Default")
      (node (ref "IC22") (pin "24") (pinfunction "OE_24") (pintype "passive"))
      (node (ref "R138") (pin "1") (pinfunction "1_1") (pintype "passive"))
    )
    (net (code "37") (name "Net-(IC23-EN)") (class "Default")
      (node (ref "C97") (pin "2") (pinfunction "2_2") (pintype "passive"))
      (node (ref "C99") (pin "2") (pinfunction "2_2") (pintype "passive"))
      (node (ref "IC23") (pin "1") (pinfunction "IN_1") (pintype "input"))
      (node (ref "IC23") (pin "3") (pinfunction "EN_3") (pintype "input"))
      (node (ref "R148") (pin "2") (pinfunction "2_2") (pintype "passive"))
      (node (ref "R150") (pin "2") (pinfunction "2_2") (pintype "passive"))
    )
    (net (code "38") (name "Net-(IC23-OUT)") (class "Default")
      (node (ref "C100") (pin "2") (pinfunction "2_2") (pintype "passive"))
      (node (ref "C98") (pin "2") (pinfunction "2_2") (pintype "passive"))
      (node (ref "IC23") (pin "5") (pinfunction "OUT_5") (pintype "output"))
      (node (ref "R150") (pin "1") (pinfunction "1_1") (pintype "passive"))
      (node (ref "XO5") (pin "4") (pinfunction "VCC_4") (pintype "passive"))
    )
    (net (code "39") (name "Net-(IC24-Vdd)") (class "Default")
      (node (ref "C107") (pin "2") (pinfunction "2_2") (pintype "passive"))
      (node (ref "C108") (pin "1") (pinfunction "1_1") (pintype "passive"))
      (node (ref "C109") (pin "1") (pinfunction "1_1") (pintype "passive"))
      (node (ref "C125") (pin "1") (pinfunction "1_1") (pintype "passive"))
      (node (ref "FR9") (pin "1") (pinfunction "1_1") (pintype "passive"))
      (node (ref "IC24") (pin "1") (pinfunction "Vdd_1") (pintype "power_in"))
      (node (ref "IC26") (pin "4") (pinfunction "VDD_4") (pintype "power_in"))
      (node (ref "R157") (pin "2") (pinfunction "2_2") (pintype "passive"))
    )
    (net (code "40") (name "Net-(IC24-Vfb)") (class "Default")
      (node (ref "C114") (pin "1") (pinfunction "1_1") (pintype "passive"))
      (node (ref "IC24") (pin "3") (pinfunction "Vfb_3") (pintype "input"))
      (node (ref "IC24") (pin "4") (pinfunction "Vout_4") (pintype "output"))
      (node (ref "R152") (pin "2") (pinfunction "2_2") (pintype "passive"))
    )
    (net (code "41") (name "Net-(IC25-CE)") (class "Default")
      (node (ref "IC25") (pin "11") (pinfunction "CE_11") (pintype "passive"))
      (node (ref "R158") (pin "1") (pinfunction "1_1") (pintype "passive"))
    )
    (net (code "42") (name "Net-(IC25-CLK)") (class "Default")
      (node (ref "C124") (pin "2") (pinfunction "2_2") (pintype "passive"))
      (node (ref "IC25") (pin "12") (pinfunction "CLK_12") (pintype "passive"))
      (node (ref "R166") (pin "2") (pinfunction "2_2") (pintype "passive"))
    )
    (net (code "43") (name "Net-(IC25-CP)") (class "Default")
      (node (ref "C121") (pin "2") (pinfunction "2_2") (pintype "passive"))
      (node (ref "C122") (pin "2") (pinfunction "2_2") (pintype "passive"))
      (node (ref "IC25") (pin "20") (pinfunction "CP_20") (pintype "passive"))
      (node (ref "R159") (pin "1") (pinfunction "1_1") (pintype "passive"))
    )
    (net (code "44") (name "Net-(IC25-DATA)") (class "Default")
      (node (ref "IC25") (pin "13") (pinfunction "DATA_13") (pintype "passive"))
      (node (ref "R168") (pin "2") (pinfunction "2_2") (pintype "passive"))
    )
    (net (code "45") (name "Net-(IC25-LE)") (class "Default")
      (node (ref "IC25") (pin "14") (pinfunction "LE_14") (pintype "passive"))
      (node (ref "R169") (pin "2") (pinfunction "2_2") (pintype "passive"))
    )
    (net (code "46") (name "Net-(IC25-REFin)") (class "Default")
      (node (ref "C116") (pin "1") (pinfunction "1_1") (pintype "passive"))
      (node (ref "IC25") (pin "8") (pinfunction "REFin_8") (pintype "passive"))
    )
    (net (code "47") (name "Net-(IC25-RFinA)") (class "Default")
      (node (ref "C105") (pin "1") (pinfunction "1_1") (pintype "passive"))
      (node (ref "IC25") (pin "5") (pinfunction "RFinA_5") (pintype "passive"))
    )
    (net (code "48") (name "Net-(IC25-RFinB)") (class "Default")
      (node (ref "C123") (pin "1") (pinfunction "1_1") (pintype "passive"))
      (node (ref "IC25") (pin "4") (pinfunction "RFinB_4") (pintype "passive"))
    )
    (net (code "49") (name "Net-(IC25-Rset)") (class "Default")
      (node (ref "IC25") (pin "19") (pinfunction "Rset_19") (pintype "passive"))
      (node (ref "R164") (pin "1") (pinfunction "1_1") (pintype "passive"))
    )
    (net (code "50") (name "Net-(IC25-Vp)") (class "Default")
      (node (ref "C113") (pin "2") (pinfunction "2_2") (pintype "passive"))
      (node (ref "C115") (pin "1") (pinfunction "1_1") (pintype "passive"))
      (node (ref "IC25") (pin "18") (pinfunction "Vp_18") (pintype "passive"))
      (node (ref "R155") (pin "1") (pinfunction "1_1") (pintype "passive"))
    )
    (net (code "51") (name "Net-(IC26-VOUT)") (class "Default")
      (node (ref "IC26") (pin "6") (pinfunction "VOUT_6") (pintype "tri_state"))
      (node (ref "R167") (pin "2") (pinfunction "2_2") (pintype "passive"))
    )
    (net (code "52") (name "Net-(J34-X)") (class "Default")
      (node (ref "J34") (pin "1") (pinfunction "X_1") (pintype "passive"))
      (node (ref "R139") (pin "1") (pinfunction "1_1") (pintype "passive"))
    )
    (net (code "53") (name "Net-(J38-Pad2)") (class "Default")
      (node (ref "J38") (pin "2") (pinfunction "2_2") (pintype "passive"))
      (node (ref "R145") (pin "1") (pinfunction "1_1") (pintype "passive"))
    )
    (net (code "54") (name "Net-(R144-Pad2)") (class "Default")
      (node (ref "R144") (pin "2") (pinfunction "2_2") (pintype "passive"))
      (node (ref "R147") (pin "1") (pinfunction "1_1") (pintype "passive"))
    )
    (net (code "55") (name "Net-(XO1-Output)") (class "Default")
      (node (ref "R136") (pin "2") (pinfunction "2_2") (pintype "passive"))
      (node (ref "XO1") (pin "3") (pinfunction "Output_3") (pintype "output"))
    )
    (net (code "56") (name "Net-(XO1-Vcc)") (class "Default")
      (node (ref "C76") (pin "2") (pinfunction "2_2") (pintype "passive"))
      (node (ref "C77") (pin "2") (pinfunction "2_2") (pintype "passive"))
      (node (ref "C78") (pin "1") (pinfunction "1_1") (pintype "passive"))
      (node (ref "R137") (pin "2") (pinfunction "2_2") (pintype "passive"))
      (node (ref "XO1") (pin "4") (pinfunction "Vcc_4") (pintype "power_in"))
    )
    (net (code "57") (name "Net-(XO2-OUT)") (class "Default")
      (node (ref "R142") (pin "2") (pinfunction "2_2") (pintype "passive"))
      (node (ref "XO2") (pin "4") (pinfunction "OUT_4") (pintype "passive"))
      (node (ref "XO3") (pin "3") (pinfunction "OUT_3") (pintype "passive"))
    )
    (net (code "58") (name "Net-(XO2-TRI-ST.)") (class "Default")
      (node (ref "R141") (pin "1") (pinfunction "1_1") (pintype "passive"))
      (node (ref "XO2") (pin "6") (pinfunction "TRI-ST._6") (pintype "passive"))
    )
    (net (code "59") (name "Net-(XO2-VDD)") (class "Default")
      (node (ref "C82") (pin "2") (pinfunction "2_2") (pintype "passive"))
      (node (ref "C83") (pin "2") (pinfunction "2_2") (pintype "passive"))
      (node (ref "R141") (pin "2") (pinfunction "2_2") (pintype "passive"))
      (node (ref "R143") (pin "1") (pinfunction "1_1") (pintype "passive"))
      (node (ref "XO2") (pin "5") (pinfunction "VDD_5") (pintype "passive"))
      (node (ref "XO3") (pin "4") (pinfunction "VDD_4") (pintype "passive"))
    )
    (net (code "60") (name "Net-(XO4-RF_OUT)") (class "Default")
      (node (ref "R146") (pin "1") (pinfunction "1_1") (pintype "passive"))
      (node (ref "XO4") (pin "6") (pinfunction "RF_OUT_6") (pintype "output"))
    )
    (net (code "61") (name "Net-(XO4-VCC)") (class "Default")
      (node (ref "C88") (pin "2") (pinfunction "2_2") (pintype "passive"))
      (node (ref "C89") (pin "2") (pinfunction "2_2") (pintype "passive"))
      (node (ref "R147") (pin "2") (pinfunction "2_2") (pintype "passive"))
      (node (ref "XO4") (pin "9") (pinfunction "VCC_9") (pintype "power_in"))
    )
    (net (code "62") (name "Net-(XO4-VC_FILTER)") (class "Default")
      (node (ref "C90") (pin "2") (pinfunction "2_2") (pintype "passive"))
      (node (ref "XO4") (pin "7") (pinfunction "VC_FILTER_7") (pintype "input"))
    )
    (net (code "63") (name "Net-(XO5-OUT)") (class "Default")
      (node (ref "R149") (pin "2") (pinfunction "2_2") (pintype "passive"))
      (node (ref "R151") (pin "1") (pinfunction "1_1") (pintype "passive"))
      (node (ref "XO5") (pin "3") (pinfunction "OUT_3") (pintype "passive"))
    )
    (net (code "64") (name "VCC2P5_VREF") (class "Default")
      (node (ref "R156") (pin "2") (pinfunction "2_2") (pintype "passive"))
    )
    (net (code "65") (name "VCC3P3_CLK") (class "Default")
      (node (ref "C101") (pin "2") (pinfunction "2_2") (pintype "passive"))
      (node (ref "C111") (pin "1") (pinfunction "1_1") (pintype "passive"))
      (node (ref "C112") (pin "1") (pinfunction "1_1") (pintype "passive"))
      (node (ref "FR5") (pin "1") (pinfunction "1_1") (pintype "passive"))
      (node (ref "FR6") (pin "1") (pinfunction "1_1") (pintype "passive"))
      (node (ref "FR7") (pin "1") (pinfunction "1_1") (pintype "passive"))
      (node (ref "FR8") (pin "1") (pinfunction "1_1") (pintype "passive"))
      (node (ref "FR9") (pin "2") (pinfunction "2_2") (pintype "passive"))
      (node (ref "IC25") (pin "16") (pinfunction "DVdd_16") (pintype "passive"))
      (node (ref "IC25") (pin "17") (pinfunction "DVdd_17") (pintype "passive"))
      (node (ref "R155") (pin "2") (pinfunction "2_2") (pintype "passive"))
      (node (ref "R158") (pin "2") (pinfunction "2_2") (pintype "passive"))
    )
    (net (code "66") (name "VCC3P3_LMK") (class "Default")
      (node (ref "C84") (pin "2") (pinfunction "2_2") (pintype "passive"))
      (node (ref "C85") (pin "2") (pinfunction "2_2") (pintype "passive"))
      (node (ref "C86") (pin "2") (pinfunction "2_2") (pintype "passive"))
      (node (ref "C87") (pin "2") (pinfunction "2_2") (pintype "passive"))
      (node (ref "FR6") (pin "2") (pinfunction "2_2") (pintype "passive"))
      (node (ref "IC22") (pin "23") (pinfunction "Vdd_23") (pintype "passive"))
      (node (ref "IC22") (pin "8") (pinfunction "Vdd_8") (pintype "passive"))
      (node (ref "R138") (pin "2") (pinfunction "2_2") (pintype "passive"))
    )
    (net (code "67") (name "VCC3P3_LMK_VDDO") (class "Default")
      (node (ref "C91") (pin "2") (pinfunction "2_2") (pintype "passive"))
      (node (ref "C92") (pin "2") (pinfunction "2_2") (pintype "passive"))
      (node (ref "C93") (pin "2") (pinfunction "2_2") (pintype "passive"))
      (node (ref "C94") (pin "2") (pinfunction "2_2") (pintype "passive"))
      (node (ref "C95") (pin "2") (pinfunction "2_2") (pintype "passive"))
      (node (ref "C96") (pin "2") (pinfunction "2_2") (pintype "passive"))
      (node (ref "FR7") (pin "2") (pinfunction "2_2") (pintype "passive"))
      (node (ref "IC22") (pin "14") (pinfunction "Vddo_14") (pintype "passive"))
      (node (ref "IC22") (pin "18") (pinfunction "Vddo_18") (pintype "passive"))
      (node (ref "IC22") (pin "2") (pinfunction "Vddo_2") (pintype "passive"))
      (node (ref "IC22") (pin "6") (pinfunction "Vddo_6") (pintype "passive"))
    )
    (net (code "68") (name "unconnected-(IC22-CLKout4-Pad17)") (class "Default")
      (node (ref "IC22") (pin "17") (pinfunction "CLKout4_17") (pintype "passive+no_connect"))
    )
    (net (code "69") (name "unconnected-(IC22-OSCin-Pad9)") (class "Default")
      (node (ref "IC22") (pin "9") (pinfunction "OSCin_9") (pintype "passive+no_connect"))
    )
    (net (code "70") (name "unconnected-(IC22-OSCout-Pad10)") (class "Default")
      (node (ref "IC22") (pin "10") (pinfunction "OSCout_10") (pintype "passive+no_connect"))
    )
    (net (code "71") (name "unconnected-(IC23-NC-Pad4)") (class "Default")
      (node (ref "IC23") (pin "4") (pinfunction "NC_4") (pintype "passive+no_connect"))
    )
    (net (code "72") (name "unconnected-(JMP2-Pad1)") (class "Default")
      (node (ref "JMP2") (pin "1") (pinfunction "1_1") (pintype "passive"))
    )
    (net (code "73") (name "unconnected-(JMP2-Pad2)") (class "Default")
      (node (ref "JMP2") (pin "2") (pinfunction "2_2") (pintype "passive"))
    )
    (net (code "74") (name "unconnected-(JMP3-Pad1)") (class "Default")
      (node (ref "JMP3") (pin "1") (pinfunction "1_1") (pintype "passive"))
    )
    (net (code "75") (name "unconnected-(JMP3-Pad2)") (class "Default")
      (node (ref "JMP3") (pin "2") (pinfunction "2_2") (pintype "passive"))
    )
    (net (code "76") (name "unconnected-(JMP4-Pad1)") (class "Default")
      (node (ref "JMP4") (pin "1") (pinfunction "1_1") (pintype "passive"))
    )
    (net (code "77") (name "unconnected-(JMP4-Pad2)") (class "Default")
      (node (ref "JMP4") (pin "2") (pinfunction "2_2") (pintype "passive"))
    )
    (net (code "78") (name "unconnected-(JMP5-Pad1)") (class "Default")
      (node (ref "JMP5") (pin "1") (pinfunction "1_1") (pintype "passive"))
    )
    (net (code "79") (name "unconnected-(JMP5-Pad2)") (class "Default")
      (node (ref "JMP5") (pin "2") (pinfunction "2_2") (pintype "passive"))
    )
    (net (code "80") (name "unconnected-(JMP6-Pad1)") (class "Default")
      (node (ref "JMP6") (pin "1") (pinfunction "1_1") (pintype "passive"))
    )
    (net (code "81") (name "unconnected-(JMP6-Pad2)") (class "Default")
      (node (ref "JMP6") (pin "2") (pinfunction "2_2") (pintype "passive"))
    )
    (net (code "82") (name "unconnected-(XO2-T.S.-Pad3)") (class "Default")
      (node (ref "XO2") (pin "3") (pinfunction "T.S._3") (pintype "passive+no_connect"))
    )
    (net (code "83") (name "unconnected-(XO4-NC-Pad2)") (class "Default")
      (node (ref "XO4") (pin "2") (pinfunction "NC_2") (pintype "passive+no_connect"))
    )
    (net (code "84") (name "unconnected-(XO4-NC-Pad3)") (class "Default")
      (node (ref "XO4") (pin "3") (pinfunction "NC_3") (pintype "passive+no_connect"))
    )
    (net (code "85") (name "unconnected-(XO4-NC-Pad5)") (class "Default")
      (node (ref "XO4") (pin "5") (pinfunction "NC_5") (pintype "passive+no_connect"))
    )
    (net (code "86") (name "unconnected-(XO4-NC-Pad8)") (class "Default")
      (node (ref "XO4") (pin "8") (pinfunction "NC_8") (pintype "passive+no_connect"))
    )
    (net (code "87") (name "unconnected-(XO4-NC-Pad10)") (class "Default")
      (node (ref "XO4") (pin "10") (pinfunction "NC_10") (pintype "passive+no_connect"))
    )
  )
)
